# LCR_0.net
KiCad netlist of a schematic drawn in Altium Designer
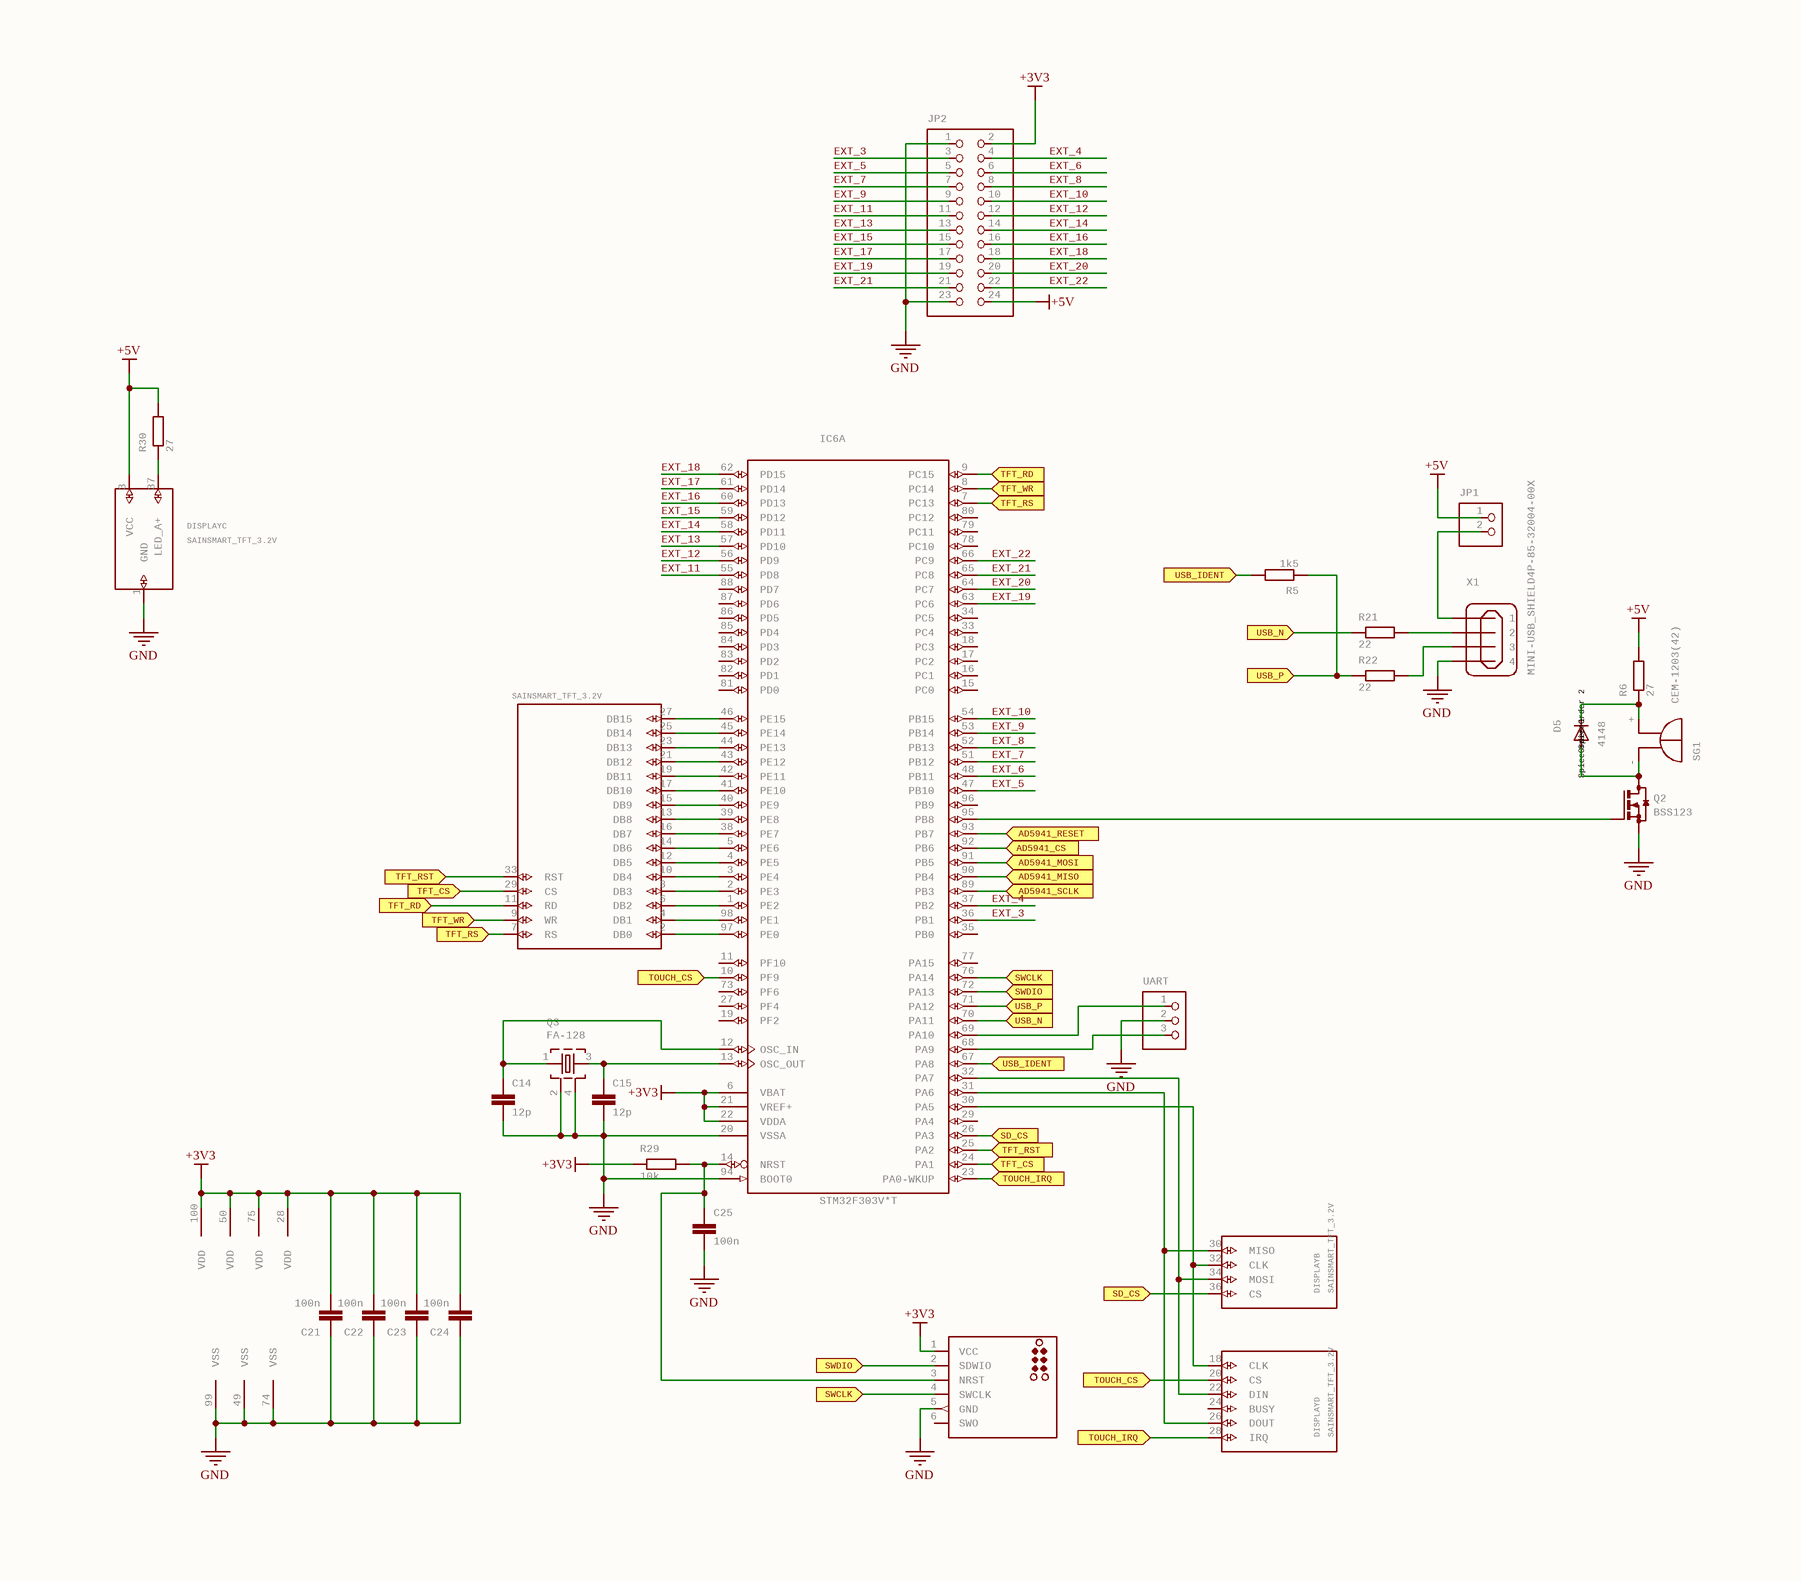
[diagram p0: LCR_0.SchDoc]

(export (version "E")
  (design (tool "Eeschema 10.0.6"))
  (components
    (comp (ref "C14")
      (value "12p")
      (footprint "C0603K")
      (description "CAPACITOR, European symbol")
      (libsource (lib "rcl") (part "C-EUC0603K"))
    )
    (comp (ref "C15")
      (value "12p")
      (footprint "C0603K")
      (description "CAPACITOR, European symbol")
      (libsource (lib "rcl") (part "C-EUC0603K"))
    )
    (comp (ref "C21")
      (value "100n")
      (footprint "C0603K")
      (description "CAPACITOR, European symbol")
      (libsource (lib "") (part "C-EUC0603K_1"))
    )
    (comp (ref "C22")
      (value "100n")
      (footprint "C0603K")
      (description "CAPACITOR, European symbol")
      (libsource (lib "") (part "C-EUC0603K_1"))
    )
    (comp (ref "C23")
      (value "100n")
      (footprint "C0603K")
      (description "CAPACITOR, European symbol")
      (libsource (lib "") (part "C-EUC0603K_1"))
    )
    (comp (ref "C24")
      (value "100n")
      (footprint "C0603K")
      (description "CAPACITOR, European symbol")
      (libsource (lib "") (part "C-EUC0603K_1"))
    )
    (comp (ref "C25")
      (value "100n")
      (footprint "C0603K")
      (description "CAPACITOR, European symbol")
      (libsource (lib "rcl") (part "C-EUC0603K"))
    )
    (comp (ref "D5")
      (value "4148")
      (footprint "SOD123")
      (description "DIODE")
      (fields (field (name "SPICEORDER1") "SpiceOrder 1") (field (name "SPICEORDER2") "SpiceOrder 2"))
      (libsource (lib "diode") (part "DIODE-SOD123"))
    )
    (comp (ref "DISPLAY")
      (value "SAINSMART_TFT_3.2V")
      (footprint "SAINSMART_ANGLED")
      (libsource (lib "sainsmart") (part "SAINSMART_TFT_3.2V"))
    )
    (comp (ref "IC6")
      (value "STM32F303V*T")
      (footprint "LQFP100")
      (libsource (lib "micro-stm_v3") (part "STM32F303V*T"))
    )
    (comp (ref "J1")
      (value "TC2030-MCP")
      (footprint "TC2030-MCP")
      (libsource (lib "tag-connect") (part "TC2030-MCP"))
    )
    (comp (ref "JP1")
      (value "PINHD-1X2")
      (footprint "1X02")
      (description "PIN HEADER")
      (fields (field (name "LIBRARYNAME") "pinhead"))
      (libsource (lib "pinhead") (part "PINHD-1X2"))
    )
    (comp (ref "JP2")
      (value "PINHD-2X12")
      (footprint "2X12")
      (description "PIN HEADER")
      (fields (field (name "LIBRARYNAME") "pinhead"))
      (libsource (lib "pinhead") (part "PINHD-2X12"))
    )
    (comp (ref "Q2")
      (value "BSS123")
      (footprint "SOT23")
      (description "N-CHANNEL MOS FET")
      (libsource (lib "transistor-small-signal") (part "BSS123"))
    )
    (comp (ref "Q3")
      (value "FA-128")
      (footprint "FA-128")
      (description "MHz RANGE CRYSTAL UNIT    Source: Epson Toyocom")
      (libsource (lib "crystal") (part "FA-128"))
    )
    (comp (ref "R5")
      (value "1k5")
      (footprint "R0603")
      (description "RESISTOR, European symbol")
      (libsource (lib "resistor") (part "R-EU_R0603"))
    )
    (comp (ref "R6")
      (value "27")
      (footprint "R1206")
      (description "RESISTOR, European symbol")
      (libsource (lib "resistor") (part "R-EU_R1206"))
    )
    (comp (ref "R21")
      (value "22")
      (footprint "R0603")
      (description "RESISTOR, European symbol")
      (libsource (lib "resistor") (part "R-EU_R0603"))
    )
    (comp (ref "R22")
      (value "22")
      (footprint "R0603")
      (description "RESISTOR, European symbol")
      (libsource (lib "resistor") (part "R-EU_R0603"))
    )
    (comp (ref "R29")
      (value "10k")
      (footprint "R0603")
      (description "RESISTOR, European symbol")
      (libsource (lib "resistor") (part "R-EU_R0603"))
    )
    (comp (ref "R30")
      (value "27")
      (footprint "R1206")
      (description "RESISTOR, European symbol")
      (libsource (lib "resistor") (part "R-EU_R1206"))
    )
    (comp (ref "SG1")
      (value "CEM-1203(42)")
      (footprint "F/QMBIII")
      (description "BUZZER    Source: Buerklin")
      (fields (field (name "MF") "MF") (field (name "MPN") "MPN"))
      (libsource (lib "buzzer") (part "F/QMBIII"))
    )
    (comp (ref "UART")
      (value "PINHD-1X3")
      (footprint "1X03")
      (description "PIN HEADER")
      (fields (field (name "LIBRARYNAME") "pinhead"))
      (libsource (lib "pinhead") (part "PINHD-1X3"))
    )
    (comp (ref "X1")
      (value "MINI-USB_SHIELD4P-85-32004-00X")
      (footprint "85-32004-00X")
      (description "MINI USB 4 Pol.   Source: www.cypressindustries.com")
      (fields (field (name "MF") "MF") (field (name "MPN") "MPN"))
      (libsource (lib "con-cypressindustries") (part "MINI-USB_SHIELD4P-85-32004-00X"))
    )
  )
  (nets
    (net (code "1") (name "+3V3") (class "Default")
      (node (ref "C21") (pin "2") (pinfunction "2_2") (pintype "passive"))
      (node (ref "C22") (pin "2") (pinfunction "2_2") (pintype "passive"))
      (node (ref "C23") (pin "2") (pinfunction "2_2") (pintype "passive"))
      (node (ref "C24") (pin "2") (pinfunction "2_2") (pintype "passive"))
      (node (ref "IC6") (pin "100") (pinfunction "VDD_100") (pintype "power_in"))
      (node (ref "IC6") (pin "21") (pinfunction "VREF+_21") (pintype "power_in"))
      (node (ref "IC6") (pin "22") (pinfunction "VDDA_22") (pintype "power_in"))
      (node (ref "IC6") (pin "28") (pinfunction "VDD_28") (pintype "power_in"))
      (node (ref "IC6") (pin "50") (pinfunction "VDD_50") (pintype "power_in"))
      (node (ref "IC6") (pin "6") (pinfunction "VBAT_6") (pintype "power_in"))
      (node (ref "IC6") (pin "75") (pinfunction "VDD_75") (pintype "power_in"))
      (node (ref "J1") (pin "1") (pinfunction "VCC_1") (pintype "passive"))
      (node (ref "JP2") (pin "2") (pinfunction "2_2") (pintype "passive"))
      (node (ref "R29") (pin "1") (pinfunction "1_1") (pintype "passive"))
    )
    (net (code "2") (name "+5V") (class "Default")
      (node (ref "DISPLAY") (pin "3") (pinfunction "VCC_3") (pintype "bidirectional"))
      (node (ref "JP1") (pin "1") (pinfunction "1_1") (pintype "passive"))
      (node (ref "JP2") (pin "24") (pinfunction "24_24") (pintype "passive"))
      (node (ref "R30") (pin "2") (pinfunction "2_2") (pintype "passive"))
      (node (ref "R6") (pin "2") (pinfunction "2_2") (pintype "passive"))
    )
    (net (code "3") (name "/AD5941_CS") (class "Default")
      (node (ref "IC6") (pin "92") (pinfunction "PB6_92") (pintype "bidirectional"))
    )
    (net (code "4") (name "/AD5941_MISO") (class "Default")
      (node (ref "IC6") (pin "90") (pinfunction "PB4_90") (pintype "bidirectional"))
    )
    (net (code "5") (name "/AD5941_MOSI") (class "Default")
      (node (ref "IC6") (pin "91") (pinfunction "PB5_91") (pintype "bidirectional"))
    )
    (net (code "6") (name "/AD5941_RESET") (class "Default")
      (node (ref "IC6") (pin "93") (pinfunction "PB7_93") (pintype "bidirectional"))
    )
    (net (code "7") (name "/AD5941_SCLK") (class "Default")
      (node (ref "IC6") (pin "89") (pinfunction "PB3_89") (pintype "bidirectional"))
    )
    (net (code "8") (name "/EXT_3") (class "Default")
      (node (ref "IC6") (pin "36") (pinfunction "PB1_36") (pintype "bidirectional"))
      (node (ref "JP2") (pin "3") (pinfunction "3_3") (pintype "passive"))
    )
    (net (code "9") (name "/EXT_4") (class "Default")
      (node (ref "IC6") (pin "37") (pinfunction "PB2_37") (pintype "bidirectional"))
      (node (ref "JP2") (pin "4") (pinfunction "4_4") (pintype "passive"))
    )
    (net (code "10") (name "/EXT_5") (class "Default")
      (node (ref "IC6") (pin "47") (pinfunction "PB10_47") (pintype "bidirectional"))
      (node (ref "JP2") (pin "5") (pinfunction "5_5") (pintype "passive"))
    )
    (net (code "11") (name "/EXT_6") (class "Default")
      (node (ref "IC6") (pin "48") (pinfunction "PB11_48") (pintype "bidirectional"))
      (node (ref "JP2") (pin "6") (pinfunction "6_6") (pintype "passive"))
    )
    (net (code "12") (name "/EXT_7") (class "Default")
      (node (ref "IC6") (pin "51") (pinfunction "PB12_51") (pintype "bidirectional"))
      (node (ref "JP2") (pin "7") (pinfunction "7_7") (pintype "passive"))
    )
    (net (code "13") (name "/EXT_8") (class "Default")
      (node (ref "IC6") (pin "52") (pinfunction "PB13_52") (pintype "bidirectional"))
      (node (ref "JP2") (pin "8") (pinfunction "8_8") (pintype "passive"))
    )
    (net (code "14") (name "/EXT_9") (class "Default")
      (node (ref "IC6") (pin "53") (pinfunction "PB14_53") (pintype "bidirectional"))
      (node (ref "JP2") (pin "9") (pinfunction "9_9") (pintype "passive"))
    )
    (net (code "15") (name "/EXT_10") (class "Default")
      (node (ref "IC6") (pin "54") (pinfunction "PB15_54") (pintype "bidirectional"))
      (node (ref "JP2") (pin "10") (pinfunction "10_10") (pintype "passive"))
    )
    (net (code "16") (name "/EXT_11") (class "Default")
      (node (ref "IC6") (pin "55") (pinfunction "PD8_55") (pintype "bidirectional"))
      (node (ref "JP2") (pin "11") (pinfunction "11_11") (pintype "passive"))
    )
    (net (code "17") (name "/EXT_12") (class "Default")
      (node (ref "IC6") (pin "56") (pinfunction "PD9_56") (pintype "bidirectional"))
      (node (ref "JP2") (pin "12") (pinfunction "12_12") (pintype "passive"))
    )
    (net (code "18") (name "/EXT_13") (class "Default")
      (node (ref "IC6") (pin "57") (pinfunction "PD10_57") (pintype "bidirectional"))
      (node (ref "JP2") (pin "13") (pinfunction "13_13") (pintype "passive"))
    )
    (net (code "19") (name "/EXT_14") (class "Default")
      (node (ref "IC6") (pin "58") (pinfunction "PD11_58") (pintype "bidirectional"))
      (node (ref "JP2") (pin "14") (pinfunction "14_14") (pintype "passive"))
    )
    (net (code "20") (name "/EXT_15") (class "Default")
      (node (ref "IC6") (pin "59") (pinfunction "PD12_59") (pintype "bidirectional"))
      (node (ref "JP2") (pin "15") (pinfunction "15_15") (pintype "passive"))
    )
    (net (code "21") (name "/EXT_16") (class "Default")
      (node (ref "IC6") (pin "60") (pinfunction "PD13_60") (pintype "bidirectional"))
      (node (ref "JP2") (pin "16") (pinfunction "16_16") (pintype "passive"))
    )
    (net (code "22") (name "/EXT_17") (class "Default")
      (node (ref "IC6") (pin "61") (pinfunction "PD14_61") (pintype "bidirectional"))
      (node (ref "JP2") (pin "17") (pinfunction "17_17") (pintype "passive"))
    )
    (net (code "23") (name "/EXT_18") (class "Default")
      (node (ref "IC6") (pin "62") (pinfunction "PD15_62") (pintype "bidirectional"))
      (node (ref "JP2") (pin "18") (pinfunction "18_18") (pintype "passive"))
    )
    (net (code "24") (name "/EXT_19") (class "Default")
      (node (ref "IC6") (pin "63") (pinfunction "PC6_63") (pintype "bidirectional"))
      (node (ref "JP2") (pin "19") (pinfunction "19_19") (pintype "passive"))
    )
    (net (code "25") (name "/EXT_20") (class "Default")
      (node (ref "IC6") (pin "64") (pinfunction "PC7_64") (pintype "bidirectional"))
      (node (ref "JP2") (pin "20") (pinfunction "20_20") (pintype "passive"))
    )
    (net (code "26") (name "/EXT_21") (class "Default")
      (node (ref "IC6") (pin "65") (pinfunction "PC8_65") (pintype "bidirectional"))
      (node (ref "JP2") (pin "21") (pinfunction "21_21") (pintype "passive"))
    )
    (net (code "27") (name "/EXT_22") (class "Default")
      (node (ref "IC6") (pin "66") (pinfunction "PC9_66") (pintype "bidirectional"))
      (node (ref "JP2") (pin "22") (pinfunction "22_22") (pintype "passive"))
    )
    (net (code "28") (name "/SD_CS") (class "Default")
      (node (ref "DISPLAY") (pin "36") (pinfunction "CS_36") (pintype "bidirectional"))
      (node (ref "IC6") (pin "26") (pinfunction "PA3_26") (pintype "bidirectional"))
    )
    (net (code "29") (name "/SWCLK") (class "Default")
      (node (ref "IC6") (pin "76") (pinfunction "PA14_76") (pintype "bidirectional"))
      (node (ref "J1") (pin "4") (pinfunction "SWCLK_4") (pintype "bidirectional"))
    )
    (net (code "30") (name "/SWDIO") (class "Default")
      (node (ref "IC6") (pin "72") (pinfunction "PA13_72") (pintype "bidirectional"))
      (node (ref "J1") (pin "2") (pinfunction "SDWIO_2") (pintype "power_in"))
    )
    (net (code "31") (name "/TFT_CS") (class "Default")
      (node (ref "DISPLAY") (pin "29") (pinfunction "CS_29") (pintype "bidirectional"))
      (node (ref "IC6") (pin "24") (pinfunction "PA1_24") (pintype "bidirectional"))
    )
    (net (code "32") (name "/TFT_RD") (class "Default")
      (node (ref "DISPLAY") (pin "11") (pinfunction "RD_11") (pintype "bidirectional"))
      (node (ref "IC6") (pin "9") (pinfunction "PC15_9") (pintype "bidirectional"))
    )
    (net (code "33") (name "/TFT_RS") (class "Default")
      (node (ref "DISPLAY") (pin "7") (pinfunction "RS_7") (pintype "bidirectional"))
      (node (ref "IC6") (pin "7") (pinfunction "PC13_7") (pintype "bidirectional"))
    )
    (net (code "34") (name "/TFT_RST") (class "Default")
      (node (ref "DISPLAY") (pin "33") (pinfunction "RST_33") (pintype "bidirectional"))
      (node (ref "IC6") (pin "25") (pinfunction "PA2_25") (pintype "bidirectional"))
    )
    (net (code "35") (name "/TFT_WR") (class "Default")
      (node (ref "DISPLAY") (pin "9") (pinfunction "WR_9") (pintype "bidirectional"))
      (node (ref "IC6") (pin "8") (pinfunction "PC14_8") (pintype "bidirectional"))
    )
    (net (code "36") (name "/TOUCH_CS") (class "Default")
      (node (ref "DISPLAY") (pin "20") (pinfunction "CS_20") (pintype "bidirectional"))
      (node (ref "IC6") (pin "10") (pinfunction "PF9_10") (pintype "bidirectional"))
    )
    (net (code "37") (name "/TOUCH_IRQ") (class "Default")
      (node (ref "DISPLAY") (pin "28") (pinfunction "IRQ_28") (pintype "bidirectional"))
      (node (ref "IC6") (pin "23") (pinfunction "PA0-WKUP_23") (pintype "bidirectional"))
    )
    (net (code "38") (name "/USB_IDENT") (class "Default")
      (node (ref "IC6") (pin "67") (pinfunction "PA8_67") (pintype "bidirectional"))
      (node (ref "R5") (pin "2") (pinfunction "2_2") (pintype "passive"))
    )
    (net (code "39") (name "/USB_N") (class "Default")
      (node (ref "IC6") (pin "70") (pinfunction "PA11_70") (pintype "bidirectional"))
      (node (ref "R21") (pin "1") (pinfunction "1_1") (pintype "passive"))
    )
    (net (code "40") (name "/USB_P") (class "Default")
      (node (ref "IC6") (pin "71") (pinfunction "PA12_71") (pintype "bidirectional"))
      (node (ref "R22") (pin "1") (pinfunction "1_1") (pintype "passive"))
      (node (ref "R5") (pin "1") (pinfunction "1_1") (pintype "passive"))
    )
    (net (code "41") (name "GND") (class "Default")
      (node (ref "C14") (pin "2") (pinfunction "2_2") (pintype "passive"))
      (node (ref "C15") (pin "2") (pinfunction "2_2") (pintype "passive"))
      (node (ref "C21") (pin "1") (pinfunction "1_1") (pintype "passive"))
      (node (ref "C22") (pin "1") (pinfunction "1_1") (pintype "passive"))
      (node (ref "C23") (pin "1") (pinfunction "1_1") (pintype "passive"))
      (node (ref "C24") (pin "1") (pinfunction "1_1") (pintype "passive"))
      (node (ref "C25") (pin "2") (pinfunction "2_2") (pintype "passive"))
      (node (ref "DISPLAY") (pin "1") (pinfunction "GND_1") (pintype "bidirectional"))
      (node (ref "IC6") (pin "20") (pinfunction "VSSA_20") (pintype "power_in"))
      (node (ref "IC6") (pin "49") (pinfunction "VSS_49") (pintype "power_in"))
      (node (ref "IC6") (pin "74") (pinfunction "VSS_74") (pintype "power_in"))
      (node (ref "IC6") (pin "94") (pinfunction "BOOT0_94") (pintype "input"))
      (node (ref "IC6") (pin "99") (pinfunction "VSS_99") (pintype "power_in"))
      (node (ref "J1") (pin "5") (pinfunction "GND_5") (pintype "output"))
      (node (ref "JP2") (pin "1") (pinfunction "1_1") (pintype "passive"))
      (node (ref "JP2") (pin "23") (pinfunction "23_23") (pintype "passive"))
      (node (ref "Q2") (pin "2") (pinfunction "S_2") (pintype "passive"))
      (node (ref "Q3") (pin "2") (pinfunction "2_2") (pintype "passive"))
      (node (ref "Q3") (pin "4") (pinfunction "4_4") (pintype "passive"))
      (node (ref "UART") (pin "2") (pinfunction "2_2") (pintype "passive"))
      (node (ref "X1") (pin "4") (pinfunction "4_4") (pintype "passive"))
    )
    (net (code "42") (name "Net-(DISPLAYA-DB0)") (class "Default")
      (node (ref "DISPLAY") (pin "2") (pinfunction "DB0_2") (pintype "bidirectional"))
      (node (ref "IC6") (pin "97") (pinfunction "PE0_97") (pintype "bidirectional"))
    )
    (net (code "43") (name "Net-(DISPLAYA-DB1)") (class "Default")
      (node (ref "DISPLAY") (pin "4") (pinfunction "DB1_4") (pintype "bidirectional"))
      (node (ref "IC6") (pin "98") (pinfunction "PE1_98") (pintype "bidirectional"))
    )
    (net (code "44") (name "Net-(DISPLAYA-DB2)") (class "Default")
      (node (ref "DISPLAY") (pin "6") (pinfunction "DB2_6") (pintype "bidirectional"))
      (node (ref "IC6") (pin "1") (pinfunction "PE2_1") (pintype "bidirectional"))
    )
    (net (code "45") (name "Net-(DISPLAYA-DB3)") (class "Default")
      (node (ref "DISPLAY") (pin "8") (pinfunction "DB3_8") (pintype "bidirectional"))
      (node (ref "IC6") (pin "2") (pinfunction "PE3_2") (pintype "bidirectional"))
    )
    (net (code "46") (name "Net-(DISPLAYA-DB4)") (class "Default")
      (node (ref "DISPLAY") (pin "10") (pinfunction "DB4_10") (pintype "bidirectional"))
      (node (ref "IC6") (pin "3") (pinfunction "PE4_3") (pintype "bidirectional"))
    )
    (net (code "47") (name "Net-(DISPLAYA-DB5)") (class "Default")
      (node (ref "DISPLAY") (pin "12") (pinfunction "DB5_12") (pintype "bidirectional"))
      (node (ref "IC6") (pin "4") (pinfunction "PE5_4") (pintype "bidirectional"))
    )
    (net (code "48") (name "Net-(DISPLAYA-DB6)") (class "Default")
      (node (ref "DISPLAY") (pin "14") (pinfunction "DB6_14") (pintype "bidirectional"))
      (node (ref "IC6") (pin "5") (pinfunction "PE6_5") (pintype "bidirectional"))
    )
    (net (code "49") (name "Net-(DISPLAYA-DB7)") (class "Default")
      (node (ref "DISPLAY") (pin "16") (pinfunction "DB7_16") (pintype "bidirectional"))
      (node (ref "IC6") (pin "38") (pinfunction "PE7_38") (pintype "bidirectional"))
    )
    (net (code "50") (name "Net-(DISPLAYA-DB8)") (class "Default")
      (node (ref "DISPLAY") (pin "13") (pinfunction "DB8_13") (pintype "bidirectional"))
      (node (ref "IC6") (pin "39") (pinfunction "PE8_39") (pintype "bidirectional"))
    )
    (net (code "51") (name "Net-(DISPLAYA-DB9)") (class "Default")
      (node (ref "DISPLAY") (pin "15") (pinfunction "DB9_15") (pintype "bidirectional"))
      (node (ref "IC6") (pin "40") (pinfunction "PE9_40") (pintype "bidirectional"))
    )
    (net (code "52") (name "Net-(DISPLAYA-DB10)") (class "Default")
      (node (ref "DISPLAY") (pin "17") (pinfunction "DB10_17") (pintype "bidirectional"))
      (node (ref "IC6") (pin "41") (pinfunction "PE10_41") (pintype "bidirectional"))
    )
    (net (code "53") (name "Net-(DISPLAYA-DB11)") (class "Default")
      (node (ref "DISPLAY") (pin "19") (pinfunction "DB11_19") (pintype "bidirectional"))
      (node (ref "IC6") (pin "42") (pinfunction "PE11_42") (pintype "bidirectional"))
    )
    (net (code "54") (name "Net-(DISPLAYA-DB12)") (class "Default")
      (node (ref "DISPLAY") (pin "21") (pinfunction "DB12_21") (pintype "bidirectional"))
      (node (ref "IC6") (pin "43") (pinfunction "PE12_43") (pintype "bidirectional"))
    )
    (net (code "55") (name "Net-(DISPLAYA-DB13)") (class "Default")
      (node (ref "DISPLAY") (pin "23") (pinfunction "DB13_23") (pintype "bidirectional"))
      (node (ref "IC6") (pin "44") (pinfunction "PE13_44") (pintype "bidirectional"))
    )
    (net (code "56") (name "Net-(DISPLAYA-DB14)") (class "Default")
      (node (ref "DISPLAY") (pin "25") (pinfunction "DB14_25") (pintype "bidirectional"))
      (node (ref "IC6") (pin "45") (pinfunction "PE14_45") (pintype "bidirectional"))
    )
    (net (code "57") (name "Net-(DISPLAYA-DB15)") (class "Default")
      (node (ref "DISPLAY") (pin "27") (pinfunction "DB15_27") (pintype "bidirectional"))
      (node (ref "IC6") (pin "46") (pinfunction "PE15_46") (pintype "bidirectional"))
    )
    (net (code "58") (name "Net-(DISPLAYB-CLK)") (class "Default")
      (node (ref "DISPLAY") (pin "18") (pinfunction "CLK_18") (pintype "bidirectional"))
      (node (ref "DISPLAY") (pin "32") (pinfunction "CLK_32") (pintype "bidirectional"))
      (node (ref "IC6") (pin "30") (pinfunction "PA5_30") (pintype "bidirectional"))
    )
    (net (code "59") (name "Net-(DISPLAYB-MISO)") (class "Default")
      (node (ref "DISPLAY") (pin "26") (pinfunction "DOUT_26") (pintype "bidirectional"))
      (node (ref "DISPLAY") (pin "30") (pinfunction "MISO_30") (pintype "bidirectional"))
      (node (ref "IC6") (pin "31") (pinfunction "PA6_31") (pintype "bidirectional"))
    )
    (net (code "60") (name "Net-(DISPLAYB-MOSI)") (class "Default")
      (node (ref "DISPLAY") (pin "22") (pinfunction "DIN_22") (pintype "bidirectional"))
      (node (ref "DISPLAY") (pin "34") (pinfunction "MOSI_34") (pintype "bidirectional"))
      (node (ref "IC6") (pin "32") (pinfunction "PA7_32") (pintype "bidirectional"))
    )
    (net (code "61") (name "Net-(DISPLAYC-LED_A+)") (class "Default")
      (node (ref "DISPLAY") (pin "37") (pinfunction "LED_A+_37") (pintype "bidirectional"))
      (node (ref "R30") (pin "1") (pinfunction "1_1") (pintype "passive"))
    )
    (net (code "62") (name "Net-(IC6A-NRST)") (class "Default")
      (node (ref "C25") (pin "1") (pinfunction "1_1") (pintype "passive"))
      (node (ref "IC6") (pin "14") (pinfunction "NRST_14") (pintype "bidirectional"))
      (node (ref "J1") (pin "3") (pinfunction "NRST_3") (pintype "power_in"))
      (node (ref "R29") (pin "2") (pinfunction "2_2") (pintype "passive"))
    )
    (net (code "63") (name "Net-(IC6A-OSC_IN)") (class "Default")
      (node (ref "C14") (pin "1") (pinfunction "1_1") (pintype "passive"))
      (node (ref "IC6") (pin "12") (pinfunction "OSC_IN_12") (pintype "bidirectional"))
      (node (ref "Q3") (pin "1") (pinfunction "1_1") (pintype "passive"))
    )
    (net (code "64") (name "Net-(IC6A-OSC_OUT)") (class "Default")
      (node (ref "C15") (pin "1") (pinfunction "1_1") (pintype "passive"))
      (node (ref "IC6") (pin "13") (pinfunction "OSC_OUT_13") (pintype "bidirectional"))
      (node (ref "Q3") (pin "3") (pinfunction "3_3") (pintype "passive"))
    )
    (net (code "65") (name "Net-(IC6A-PA9)") (class "Default")
      (node (ref "IC6") (pin "68") (pinfunction "PA9_68") (pintype "bidirectional"))
      (node (ref "UART") (pin "3") (pinfunction "3_3") (pintype "passive"))
    )
    (net (code "66") (name "Net-(IC6A-PA10)") (class "Default")
      (node (ref "IC6") (pin "69") (pinfunction "PA10_69") (pintype "bidirectional"))
      (node (ref "UART") (pin "1") (pinfunction "1_1") (pintype "passive"))
    )
    (net (code "67") (name "Net-(IC6A-PB8)") (class "Default")
      (node (ref "IC6") (pin "95") (pinfunction "PB8_95") (pintype "bidirectional"))
      (node (ref "Q2") (pin "1") (pinfunction "G_1") (pintype "passive"))
    )
    (net (code "68") (name "Net-(JP1-Pad2)") (class "Default")
      (node (ref "JP1") (pin "2") (pinfunction "2_2") (pintype "passive"))
      (node (ref "X1") (pin "1") (pinfunction "1_1") (pintype "passive"))
    )
    (net (code "69") (name "Net-(Q2-D)") (class "Default")
      (node (ref "D5") (pin "A") (pinfunction "A_A") (pintype "passive"))
      (node (ref "Q2") (pin "3") (pinfunction "D_3") (pintype "passive"))
      (node (ref "SG1") (pin "-") (pinfunction "+_-") (pintype "passive"))
    )
    (net (code "70") (name "Net-(R21-Pad2)") (class "Default")
      (node (ref "R21") (pin "2") (pinfunction "2_2") (pintype "passive"))
      (node (ref "X1") (pin "2") (pinfunction "2_2") (pintype "passive"))
    )
    (net (code "71") (name "Net-(R22-Pad2)") (class "Default")
      (node (ref "R22") (pin "2") (pinfunction "2_2") (pintype "passive"))
      (node (ref "X1") (pin "3") (pinfunction "3_3") (pintype "passive"))
    )
    (net (code "72") (name "Net-(SG1--)") (class "Default")
      (node (ref "D5") (pin "C") (pinfunction "C_C") (pintype "passive"))
      (node (ref "R6") (pin "1") (pinfunction "1_1") (pintype "passive"))
      (node (ref "SG1") (pin "+") (pinfunction "-_+") (pintype "passive"))
    )
    (net (code "73") (name "unconnected-(DISPLAYD-BUSY-Pad24)") (class "Default")
      (node (ref "DISPLAY") (pin "24") (pinfunction "BUSY_24") (pintype "bidirectional"))
    )
    (net (code "74") (name "unconnected-(IC6A-PA4-Pad29)") (class "Default")
      (node (ref "IC6") (pin "29") (pinfunction "PA4_29") (pintype "bidirectional"))
    )
    (net (code "75") (name "unconnected-(IC6A-PA15-Pad77)") (class "Default")
      (node (ref "IC6") (pin "77") (pinfunction "PA15_77") (pintype "bidirectional"))
    )
    (net (code "76") (name "unconnected-(IC6A-PB0-Pad35)") (class "Default")
      (node (ref "IC6") (pin "35") (pinfunction "PB0_35") (pintype "bidirectional"))
    )
    (net (code "77") (name "unconnected-(IC6A-PB9-Pad96)") (class "Default")
      (node (ref "IC6") (pin "96") (pinfunction "PB9_96") (pintype "bidirectional"))
    )
    (net (code "78") (name "unconnected-(IC6A-PC0-Pad15)") (class "Default")
      (node (ref "IC6") (pin "15") (pinfunction "PC0_15") (pintype "bidirectional"))
    )
    (net (code "79") (name "unconnected-(IC6A-PC1-Pad16)") (class "Default")
      (node (ref "IC6") (pin "16") (pinfunction "PC1_16") (pintype "bidirectional"))
    )
    (net (code "80") (name "unconnected-(IC6A-PC2-Pad17)") (class "Default")
      (node (ref "IC6") (pin "17") (pinfunction "PC2_17") (pintype "bidirectional"))
    )
    (net (code "81") (name "unconnected-(IC6A-PC3-Pad18)") (class "Default")
      (node (ref "IC6") (pin "18") (pinfunction "PC3_18") (pintype "bidirectional"))
    )
    (net (code "82") (name "unconnected-(IC6A-PC4-Pad33)") (class "Default")
      (node (ref "IC6") (pin "33") (pinfunction "PC4_33") (pintype "bidirectional"))
    )
    (net (code "83") (name "unconnected-(IC6A-PC5-Pad34)") (class "Default")
      (node (ref "IC6") (pin "34") (pinfunction "PC5_34") (pintype "bidirectional"))
    )
    (net (code "84") (name "unconnected-(IC6A-PC10-Pad78)") (class "Default")
      (node (ref "IC6") (pin "78") (pinfunction "PC10_78") (pintype "bidirectional"))
    )
    (net (code "85") (name "unconnected-(IC6A-PC11-Pad79)") (class "Default")
      (node (ref "IC6") (pin "79") (pinfunction "PC11_79") (pintype "bidirectional"))
    )
    (net (code "86") (name "unconnected-(IC6A-PC12-Pad80)") (class "Default")
      (node (ref "IC6") (pin "80") (pinfunction "PC12_80") (pintype "bidirectional"))
    )
    (net (code "87") (name "unconnected-(IC6A-PD0-Pad81)") (class "Default")
      (node (ref "IC6") (pin "81") (pinfunction "PD0_81") (pintype "bidirectional"))
    )
    (net (code "88") (name "unconnected-(IC6A-PD1-Pad82)") (class "Default")
      (node (ref "IC6") (pin "82") (pinfunction "PD1_82") (pintype "bidirectional"))
    )
    (net (code "89") (name "unconnected-(IC6A-PD2-Pad83)") (class "Default")
      (node (ref "IC6") (pin "83") (pinfunction "PD2_83") (pintype "bidirectional"))
    )
    (net (code "90") (name "unconnected-(IC6A-PD3-Pad84)") (class "Default")
      (node (ref "IC6") (pin "84") (pinfunction "PD3_84") (pintype "bidirectional"))
    )
    (net (code "91") (name "unconnected-(IC6A-PD4-Pad85)") (class "Default")
      (node (ref "IC6") (pin "85") (pinfunction "PD4_85") (pintype "bidirectional"))
    )
    (net (code "92") (name "unconnected-(IC6A-PD5-Pad86)") (class "Default")
      (node (ref "IC6") (pin "86") (pinfunction "PD5_86") (pintype "bidirectional"))
    )
    (net (code "93") (name "unconnected-(IC6A-PD6-Pad87)") (class "Default")
      (node (ref "IC6") (pin "87") (pinfunction "PD6_87") (pintype "bidirectional"))
    )
    (net (code "94") (name "unconnected-(IC6A-PD7-Pad88)") (class "Default")
      (node (ref "IC6") (pin "88") (pinfunction "PD7_88") (pintype "bidirectional"))
    )
    (net (code "95") (name "unconnected-(IC6A-PF2-Pad19)") (class "Default")
      (node (ref "IC6") (pin "19") (pinfunction "PF2_19") (pintype "bidirectional"))
    )
    (net (code "96") (name "unconnected-(IC6A-PF4-Pad27)") (class "Default")
      (node (ref "IC6") (pin "27") (pinfunction "PF4_27") (pintype "bidirectional"))
    )
    (net (code "97") (name "unconnected-(IC6A-PF6-Pad73)") (class "Default")
      (node (ref "IC6") (pin "73") (pinfunction "PF6_73") (pintype "bidirectional"))
    )
    (net (code "98") (name "unconnected-(IC6A-PF10-Pad11)") (class "Default")
      (node (ref "IC6") (pin "11") (pinfunction "PF10_11") (pintype "bidirectional"))
    )
    (net (code "99") (name "unconnected-(J1-SWO-Pad6)") (class "Default")
      (node (ref "J1") (pin "6") (pinfunction "SWO_6") (pintype "bidirectional"))
    )
  )
)
